# OpenLog.net
KiCad netlist of a schematic drawn in EAGLE
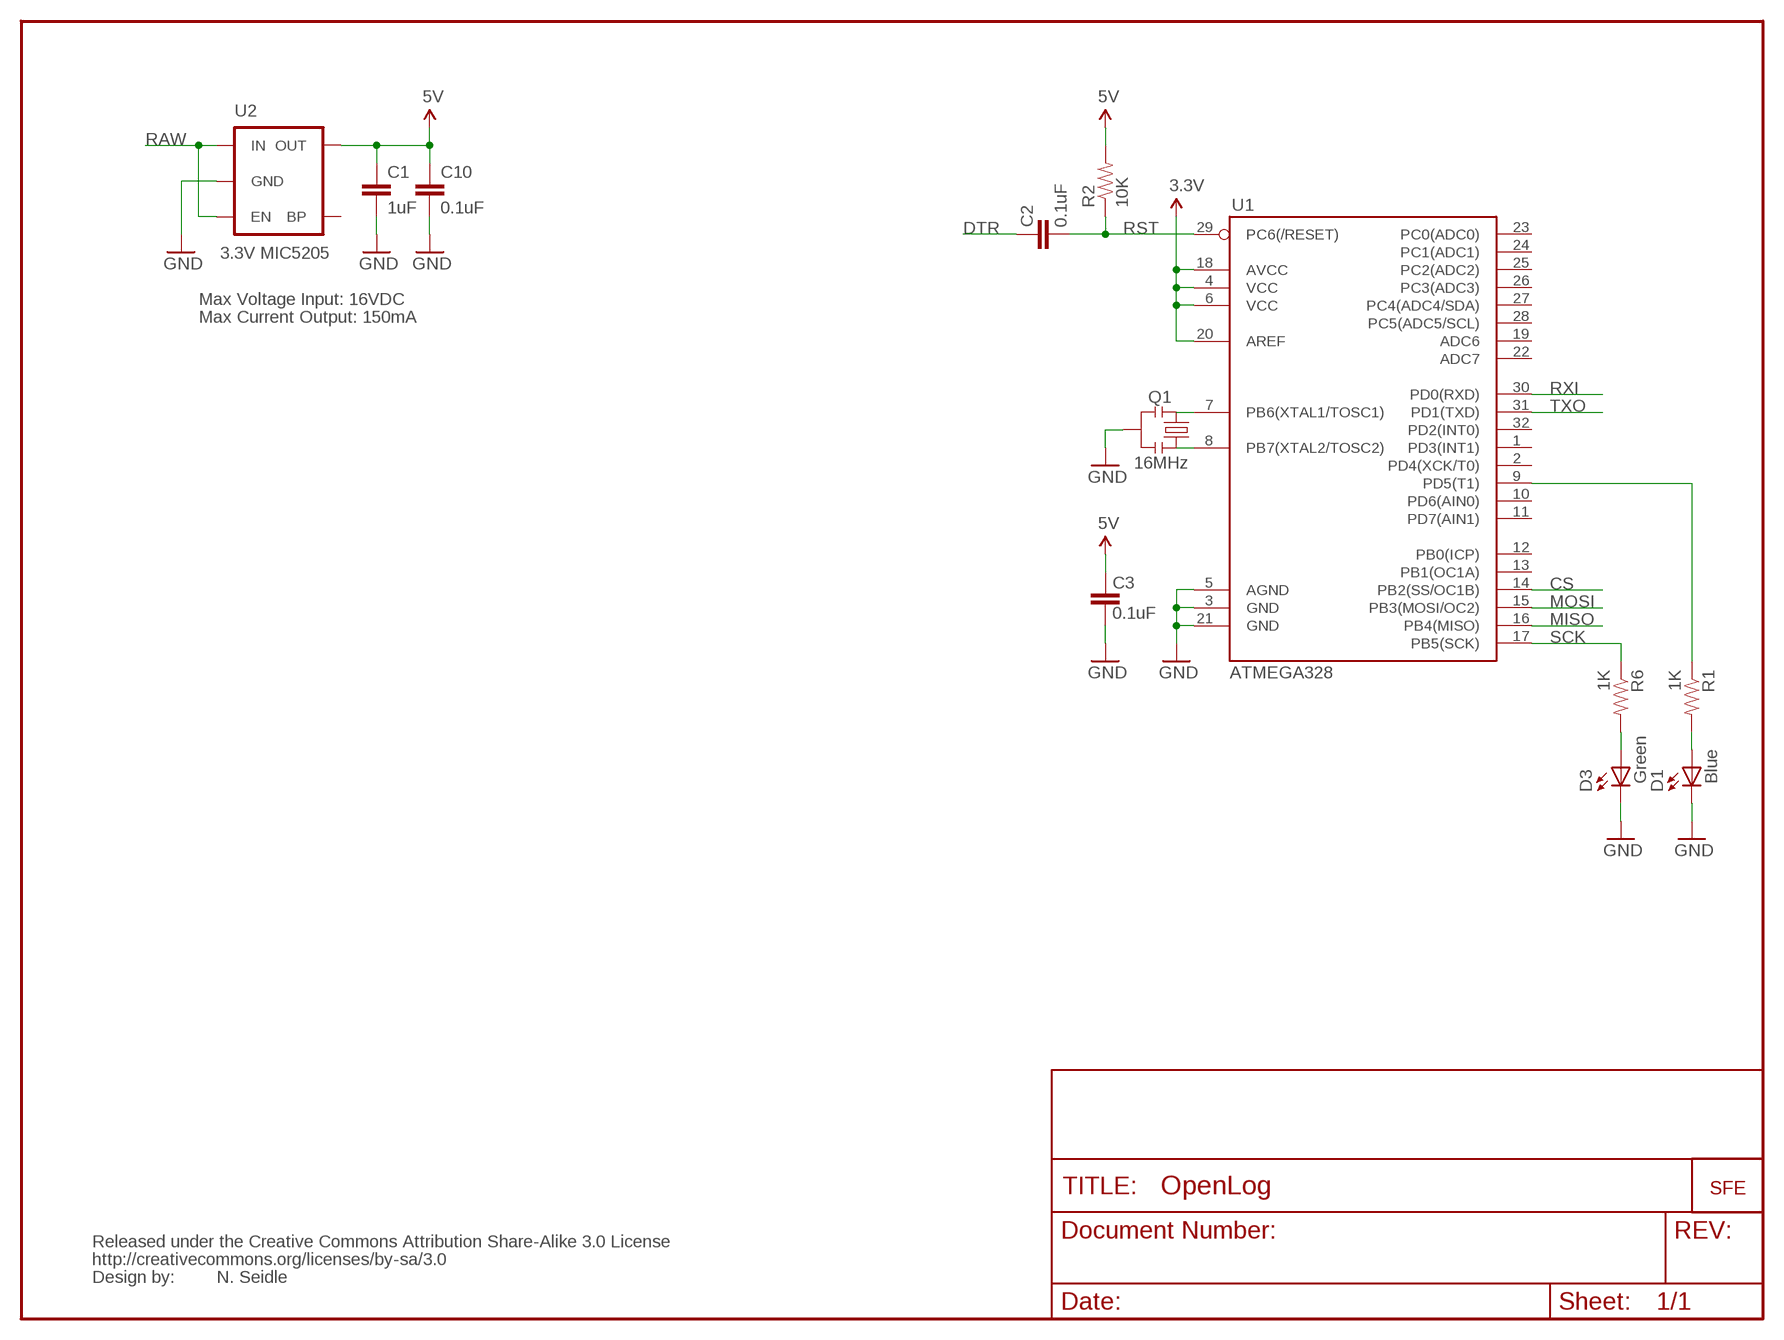
[diagram p0: schematic, sheet 1]

(export (version "E")
  (design (tool "Eeschema 10.0.6"))
  (components
    (comp (ref "C1")
      (value "1uF")
      (footprint "eagle-import:0402-CAP")
      (libsource (lib "eagle-import") (part "CAP0402-CAP"))
    )
    (comp (ref "C2")
      (value "0.1uF")
      (footprint "eagle-import:0402-CAP")
      (libsource (lib "eagle-import") (part "CAP0402-CAP"))
    )
    (comp (ref "C3")
      (value "0.1uF")
      (footprint "eagle-import:0402-CAP")
      (libsource (lib "eagle-import") (part "CAP0402-CAP"))
    )
    (comp (ref "C10")
      (value "0.1uF")
      (footprint "eagle-import:0402-CAP")
      (libsource (lib "eagle-import") (part "CAP0402-CAP"))
    )
    (comp (ref "D1")
      (value "Blue")
      (footprint "eagle-import:LED-0603")
      (libsource (lib "eagle-import") (part "LED0603"))
    )
    (comp (ref "D3")
      (value "Green")
      (footprint "eagle-import:LED-0603")
      (libsource (lib "eagle-import") (part "LED0603"))
    )
    (comp (ref "Q1")
      (value "16MHz")
      (footprint "eagle-import:RESONATOR-SMD")
      (libsource (lib "eagle-import") (part "RESONATORSMD"))
    )
    (comp (ref "R1")
      (value "1K")
      (footprint "eagle-import:0402-RES")
      (libsource (lib "eagle-import") (part "RESISTOR0402-RES"))
    )
    (comp (ref "R2")
      (value "10K")
      (footprint "eagle-import:0402-RES")
      (libsource (lib "eagle-import") (part "RESISTOR0402-RES"))
    )
    (comp (ref "R6")
      (value "1K")
      (footprint "eagle-import:0402-RES")
      (libsource (lib "eagle-import") (part "RESISTOR0402-RES"))
    )
    (comp (ref "U$1")
      (value "LOGO-SFESK")
      (footprint "eagle-import:SFE-LOGO-FLAME")
      (libsource (lib "eagle-import") (part "LOGO-SFESK"))
    )
    (comp (ref "U$2")
      (value "CREATIVE_COMMONS")
      (footprint "eagle-import:CREATIVE_COMMONS")
      (libsource (lib "eagle-import") (part "CREATIVE_COMMONS"))
    )
    (comp (ref "U1")
      (value "ATMEGA328")
      (footprint "eagle-import:TQFP32-08")
      (libsource (lib "eagle-import") (part "ATMEGA168"))
    )
    (comp (ref "U2")
      (value "3.3V MIC5205")
      (footprint "eagle-import:SOT23-5")
      (libsource (lib "eagle-import") (part "V_REG_LDOSMD"))
    )
  )
  (nets
    (net (code "1") (name "/CS") (class "Default")
      (node (ref "U1") (pin "14") (pinfunction "PB2(SS/OC1B)_14") (pintype "bidirectional"))
    )
    (net (code "2") (name "/DTR") (class "Default")
      (node (ref "C2") (pin "2") (pinfunction "2_2") (pintype "passive"))
    )
    (net (code "3") (name "/MISO") (class "Default")
      (node (ref "U1") (pin "16") (pinfunction "PB4(MISO)_16") (pintype "bidirectional"))
    )
    (net (code "4") (name "/MOSI") (class "Default")
      (node (ref "U1") (pin "15") (pinfunction "PB3(MOSI/OC2)_15") (pintype "bidirectional"))
    )
    (net (code "5") (name "/RAW") (class "Default")
      (node (ref "U2") (pin "1") (pinfunction "IN_1") (pintype "input"))
      (node (ref "U2") (pin "3") (pinfunction "EN_3") (pintype "input"))
    )
    (net (code "6") (name "/RST") (class "Default")
      (node (ref "C2") (pin "1") (pinfunction "1_1") (pintype "passive"))
      (node (ref "R2") (pin "1") (pinfunction "1_1") (pintype "passive"))
      (node (ref "U1") (pin "29") (pinfunction "PC6(/RESET)_29") (pintype "bidirectional"))
    )
    (net (code "7") (name "/RXI") (class "Default")
      (node (ref "U1") (pin "30") (pinfunction "PD0(RXD)_30") (pintype "bidirectional"))
    )
    (net (code "8") (name "/SCK") (class "Default")
      (node (ref "R6") (pin "1") (pinfunction "1_1") (pintype "passive"))
      (node (ref "U1") (pin "17") (pinfunction "PB5(SCK)_17") (pintype "bidirectional"))
    )
    (net (code "9") (name "/TXO") (class "Default")
      (node (ref "U1") (pin "31") (pinfunction "PD1(TXD)_31") (pintype "bidirectional"))
    )
    (net (code "10") (name "3.3V") (class "Default")
      (node (ref "U1") (pin "18") (pinfunction "AVCC_18") (pintype "bidirectional"))
      (node (ref "U1") (pin "20") (pinfunction "AREF_20") (pintype "bidirectional"))
      (node (ref "U1") (pin "4") (pinfunction "VCC_4") (pintype "bidirectional"))
      (node (ref "U1") (pin "6") (pinfunction "VCC_6") (pintype "bidirectional"))
    )
    (net (code "11") (name "5V") (class "Default")
      (node (ref "C1") (pin "1") (pinfunction "1_1") (pintype "passive"))
      (node (ref "C10") (pin "1") (pinfunction "1_1") (pintype "passive"))
      (node (ref "C3") (pin "2") (pinfunction "2_2") (pintype "passive"))
      (node (ref "R2") (pin "2") (pinfunction "2_2") (pintype "passive"))
      (node (ref "U2") (pin "5") (pinfunction "OUT_5") (pintype "passive"))
    )
    (net (code "12") (name "GND") (class "Default")
      (node (ref "C1") (pin "2") (pinfunction "2_2") (pintype "passive"))
      (node (ref "C10") (pin "2") (pinfunction "2_2") (pintype "passive"))
      (node (ref "C3") (pin "1") (pinfunction "1_1") (pintype "passive"))
      (node (ref "D1") (pin "C") (pinfunction "C_C") (pintype "passive"))
      (node (ref "D3") (pin "C") (pinfunction "C_C") (pintype "passive"))
      (node (ref "Q1") (pin "2") (pinfunction "2_2") (pintype "passive"))
      (node (ref "U1") (pin "21") (pinfunction "GND_21") (pintype "bidirectional"))
      (node (ref "U1") (pin "3") (pinfunction "GND_3") (pintype "bidirectional"))
      (node (ref "U1") (pin "5") (pinfunction "AGND_5") (pintype "bidirectional"))
      (node (ref "U2") (pin "2") (pinfunction "GND_2") (pintype "input"))
    )
    (net (code "13") (name "Net-(D1-PadA)") (class "Default")
      (node (ref "D1") (pin "A") (pinfunction "A_A") (pintype "passive"))
      (node (ref "R1") (pin "2") (pinfunction "2_2") (pintype "passive"))
    )
    (net (code "14") (name "Net-(D3-PadA)") (class "Default")
      (node (ref "D3") (pin "A") (pinfunction "A_A") (pintype "passive"))
      (node (ref "R6") (pin "2") (pinfunction "2_2") (pintype "passive"))
    )
    (net (code "15") (name "Net-(U1-PB6(XTAL1{slash}TOSC1))") (class "Default")
      (node (ref "Q1") (pin "3") (pinfunction "3_3") (pintype "passive"))
      (node (ref "U1") (pin "7") (pinfunction "PB6(XTAL1/TOSC1)_7") (pintype "bidirectional"))
    )
    (net (code "16") (name "Net-(U1-PB7(XTAL2{slash}TOSC2))") (class "Default")
      (node (ref "Q1") (pin "1") (pinfunction "1_1") (pintype "passive"))
      (node (ref "U1") (pin "8") (pinfunction "PB7(XTAL2/TOSC2)_8") (pintype "bidirectional"))
    )
    (net (code "17") (name "Net-(U1-PD5(T1))") (class "Default")
      (node (ref "R1") (pin "1") (pinfunction "1_1") (pintype "passive"))
      (node (ref "U1") (pin "9") (pinfunction "PD5(T1)_9") (pintype "bidirectional"))
    )
    (net (code "18") (name "unconnected-(U1-ADC6-Pad19)") (class "Default")
      (node (ref "U1") (pin "19") (pinfunction "ADC6_19") (pintype "bidirectional"))
    )
    (net (code "19") (name "unconnected-(U1-ADC7-Pad22)") (class "Default")
      (node (ref "U1") (pin "22") (pinfunction "ADC7_22") (pintype "bidirectional"))
    )
    (net (code "20") (name "unconnected-(U1-PB0(ICP)-Pad12)") (class "Default")
      (node (ref "U1") (pin "12") (pinfunction "PB0(ICP)_12") (pintype "bidirectional"))
    )
    (net (code "21") (name "unconnected-(U1-PB1(OC1A)-Pad13)") (class "Default")
      (node (ref "U1") (pin "13") (pinfunction "PB1(OC1A)_13") (pintype "bidirectional"))
    )
    (net (code "22") (name "unconnected-(U1-PC0(ADC0)-Pad23)") (class "Default")
      (node (ref "U1") (pin "23") (pinfunction "PC0(ADC0)_23") (pintype "bidirectional"))
    )
    (net (code "23") (name "unconnected-(U1-PC1(ADC1)-Pad24)") (class "Default")
      (node (ref "U1") (pin "24") (pinfunction "PC1(ADC1)_24") (pintype "bidirectional"))
    )
    (net (code "24") (name "unconnected-(U1-PC2(ADC2)-Pad25)") (class "Default")
      (node (ref "U1") (pin "25") (pinfunction "PC2(ADC2)_25") (pintype "bidirectional"))
    )
    (net (code "25") (name "unconnected-(U1-PC3(ADC3)-Pad26)") (class "Default")
      (node (ref "U1") (pin "26") (pinfunction "PC3(ADC3)_26") (pintype "bidirectional"))
    )
    (net (code "26") (name "unconnected-(U1-PC4(ADC4{slash}SDA)-Pad27)") (class "Default")
      (node (ref "U1") (pin "27") (pinfunction "PC4(ADC4/SDA)_27") (pintype "bidirectional"))
    )
    (net (code "27") (name "unconnected-(U1-PC5(ADC5{slash}SCL)-Pad28)") (class "Default")
      (node (ref "U1") (pin "28") (pinfunction "PC5(ADC5/SCL)_28") (pintype "bidirectional"))
    )
    (net (code "28") (name "unconnected-(U1-PD2(INT0)-Pad32)") (class "Default")
      (node (ref "U1") (pin "32") (pinfunction "PD2(INT0)_32") (pintype "bidirectional"))
    )
    (net (code "29") (name "unconnected-(U1-PD3(INT1)-Pad1)") (class "Default")
      (node (ref "U1") (pin "1") (pinfunction "PD3(INT1)_1") (pintype "bidirectional"))
    )
    (net (code "30") (name "unconnected-(U1-PD4(XCK{slash}T0)-Pad2)") (class "Default")
      (node (ref "U1") (pin "2") (pinfunction "PD4(XCK/T0)_2") (pintype "bidirectional"))
    )
    (net (code "31") (name "unconnected-(U1-PD6(AIN0)-Pad10)") (class "Default")
      (node (ref "U1") (pin "10") (pinfunction "PD6(AIN0)_10") (pintype "bidirectional"))
    )
    (net (code "32") (name "unconnected-(U1-PD7(AIN1)-Pad11)") (class "Default")
      (node (ref "U1") (pin "11") (pinfunction "PD7(AIN1)_11") (pintype "bidirectional"))
    )
    (net (code "33") (name "unconnected-(U2-BP-Pad4)") (class "Default")
      (node (ref "U2") (pin "4") (pinfunction "BP_4") (pintype "input"))
    )
  )
)
